# TinyGame_RC1.net
KiCad netlist of a schematic drawn in EAGLE
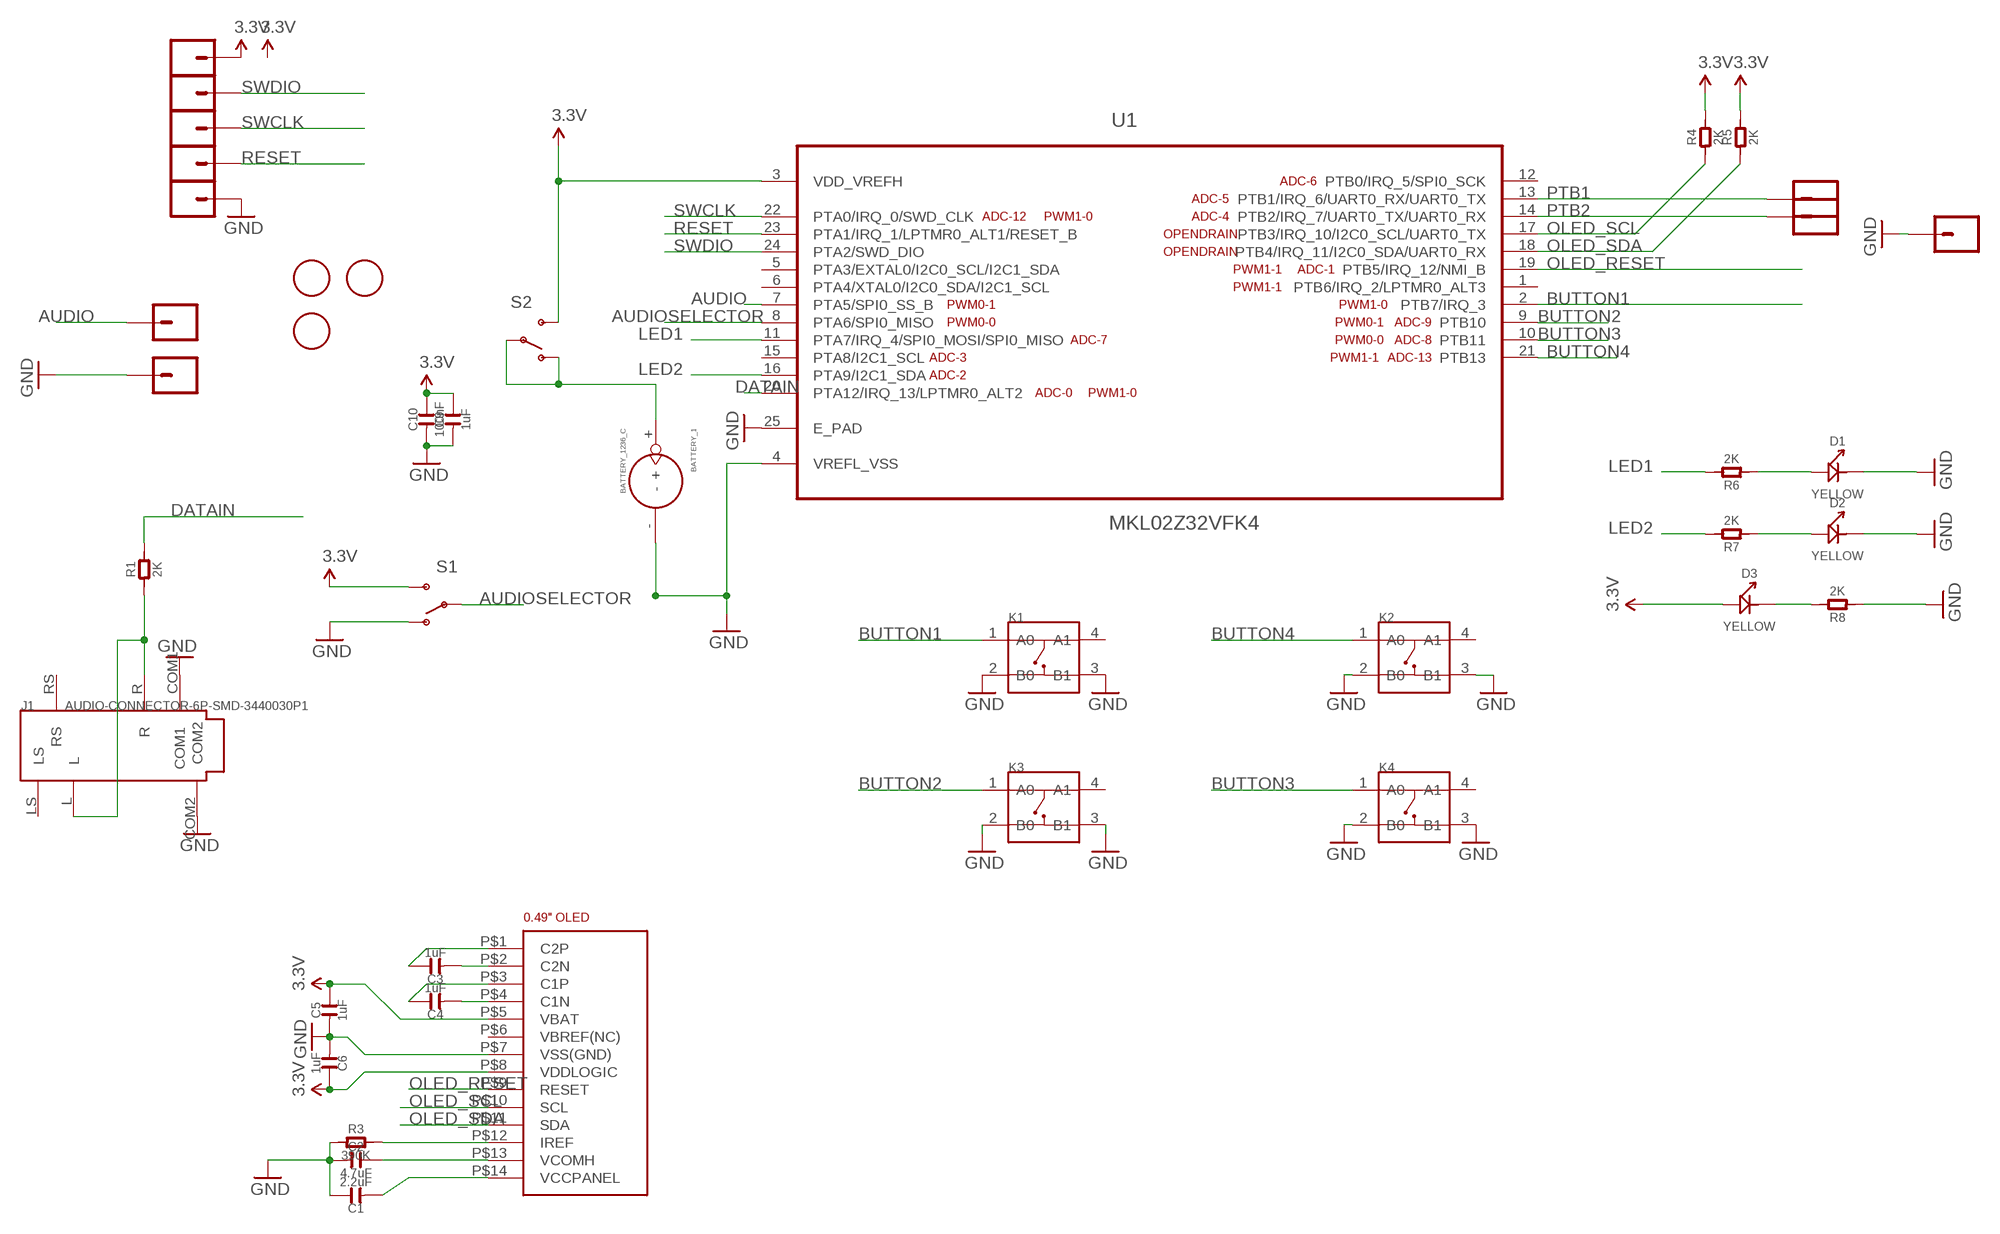
[diagram p0: schematic, sheet 1]

(export (version "E")
  (design (tool "Eeschema 10.0.6"))
  (components
    (comp (ref "AUDIOGND")
      (value "M01SMD-4.5X1.5")
      (footprint "eagle-import:PAD-1.5X4.5")
      (libsource (lib "eagle-import") (part "M01SMD-4.5X1.5"))
    )
    (comp (ref "AUDIOSIG")
      (value "M01SMD-4.5X1.5")
      (footprint "eagle-import:PAD-1.5X4.5")
      (libsource (lib "eagle-import") (part "M01SMD-4.5X1.5"))
    )
    (comp (ref "BATTERY_1")
      (value "BATTERY_1236_C")
      (footprint "eagle-import:BATTERY_1236_C")
      (libsource (lib "eagle-import") (part "BATTERY_1236_C"))
    )
    (comp (ref "C1")
      (value "2.2uF")
      (footprint "eagle-import:C0603")
      (libsource (lib "eagle-import") (part "C-0603"))
    )
    (comp (ref "C2")
      (value "4.7uF")
      (footprint "eagle-import:C0603")
      (libsource (lib "eagle-import") (part "C-0603"))
    )
    (comp (ref "C3")
      (value "1uF")
      (footprint "eagle-import:C0603")
      (libsource (lib "eagle-import") (part "C-0603"))
    )
    (comp (ref "C4")
      (value "1uF")
      (footprint "eagle-import:C0603")
      (libsource (lib "eagle-import") (part "C-0603"))
    )
    (comp (ref "C5")
      (value "1uF")
      (footprint "eagle-import:C0603")
      (libsource (lib "eagle-import") (part "C-0603"))
    )
    (comp (ref "C6")
      (value "1uF")
      (footprint "eagle-import:C0603")
      (libsource (lib "eagle-import") (part "C-0603"))
    )
    (comp (ref "C9")
      (value "1uF")
      (footprint "eagle-import:C0603")
      (libsource (lib "eagle-import") (part "C-0603"))
    )
    (comp (ref "C10")
      (value "100nF")
      (footprint "eagle-import:C0603")
      (libsource (lib "eagle-import") (part "C-0603"))
    )
    (comp (ref "D1")
      (value "YELLOW")
      (footprint "eagle-import:LED0603")
      (libsource (lib "eagle-import") (part "LED"))
    )
    (comp (ref "D2")
      (value "YELLOW")
      (footprint "eagle-import:LED0603")
      (libsource (lib "eagle-import") (part "LED"))
    )
    (comp (ref "D3")
      (value "YELLOW")
      (footprint "eagle-import:LED0603")
      (libsource (lib "eagle-import") (part "LED"))
    )
    (comp (ref "J1")
      (value "AUDIO-CONNECTOR-6P-SMD-3440030P1")
      (footprint "eagle-import:6P-SMD-3.5")
      (libsource (lib "eagle-import") (part "AUDIO-CONNECTOR-6P-SMD-3440030P1"))
    )
    (comp (ref "K1")
      (value "BUTTON-4P-3100010P1")
      (footprint "eagle-import:4P-SMD-6.0X6.0X5.0H")
      (libsource (lib "eagle-import") (part "BUTTON-4P-3100010P1"))
    )
    (comp (ref "K2")
      (value "BUTTON-4P-3100010P1")
      (footprint "eagle-import:4P-SMD-6.0X6.0X5.0H")
      (libsource (lib "eagle-import") (part "BUTTON-4P-3100010P1"))
    )
    (comp (ref "K3")
      (value "BUTTON-4P-3100010P1")
      (footprint "eagle-import:4P-SMD-6.0X6.0X5.0H")
      (libsource (lib "eagle-import") (part "BUTTON-4P-3100010P1"))
    )
    (comp (ref "K4")
      (value "BUTTON-4P-3100010P1")
      (footprint "eagle-import:4P-SMD-6.0X6.0X5.0H")
      (libsource (lib "eagle-import") (part "BUTTON-4P-3100010P1"))
    )
    (comp (ref "PTA6_MISO1")
      (value "M01SMD-4.5X1.5")
      (footprint "eagle-import:PAD-1.5X4.5")
      (libsource (lib "eagle-import") (part "M01SMD-4.5X1.5"))
    )
    (comp (ref "PTA6_MISO2")
      (value "M01SMD-4.5X1.5")
      (footprint "eagle-import:PAD-1.5X4.5")
      (libsource (lib "eagle-import") (part "M01SMD-4.5X1.5"))
    )
    (comp (ref "PTA6_MISO3")
      (value "M01SMD-4.5X1.5")
      (footprint "eagle-import:PAD-1.5X4.5")
      (libsource (lib "eagle-import") (part "M01SMD-4.5X1.5"))
    )
    (comp (ref "PTA6_MISO4")
      (value "M01SMD-4.5X1.5")
      (footprint "eagle-import:PAD-1.5X4.5")
      (libsource (lib "eagle-import") (part "M01SMD-4.5X1.5"))
    )
    (comp (ref "PTA6_MISO5")
      (value "M01SMD-4.5X1.5")
      (footprint "eagle-import:PAD-1.5X4.5")
      (libsource (lib "eagle-import") (part "M01SMD-4.5X1.5"))
    )
    (comp (ref "PTB1_RXTX")
      (value "M01SMD-4.5X1.5")
      (footprint "eagle-import:PAD-1.5X4.5")
      (libsource (lib "eagle-import") (part "M01SMD-4.5X1.5"))
    )
    (comp (ref "PTB2_TXRX")
      (value "M01SMD-4.5X1.5")
      (footprint "eagle-import:PAD-1.5X4.5")
      (libsource (lib "eagle-import") (part "M01SMD-4.5X1.5"))
    )
    (comp (ref "PTB2_TXRX2")
      (value "M01SMD-4.5X1.5")
      (footprint "eagle-import:PAD-1.5X4.5")
      (libsource (lib "eagle-import") (part "M01SMD-4.5X1.5"))
    )
    (comp (ref "R1")
      (value "2K")
      (footprint "eagle-import:R0603")
      (libsource (lib "eagle-import") (part "R-0603"))
    )
    (comp (ref "R3")
      (value "390K")
      (footprint "eagle-import:R0603")
      (libsource (lib "eagle-import") (part "R-0603"))
    )
    (comp (ref "R4")
      (value "2K")
      (footprint "eagle-import:R0603")
      (libsource (lib "eagle-import") (part "R-0603"))
    )
    (comp (ref "R5")
      (value "2K")
      (footprint "eagle-import:R0603")
      (libsource (lib "eagle-import") (part "R-0603"))
    )
    (comp (ref "R6")
      (value "2K")
      (footprint "eagle-import:R0603")
      (libsource (lib "eagle-import") (part "R-0603"))
    )
    (comp (ref "R7")
      (value "2K")
      (footprint "eagle-import:R0603")
      (libsource (lib "eagle-import") (part "R-0603"))
    )
    (comp (ref "R8")
      (value "2K")
      (footprint "eagle-import:R0603")
      (libsource (lib "eagle-import") (part "R-0603"))
    )
    (comp (ref "S1")
      (value "SWITCH-SPDT-SMD-A")
      (footprint "eagle-import:SWITCH-SPST-SMD-A")
      (libsource (lib "eagle-import") (part "SWITCH-SPDT-SMD-A"))
    )
    (comp (ref "S2")
      (value "SWITCH-SPDT-SMD-A")
      (footprint "eagle-import:SWITCH-SPST-SMD-A")
      (libsource (lib "eagle-import") (part "SWITCH-SPDT-SMD-A"))
    )
    (comp (ref "U$1")
      (value "0.49\"OLEDFOLDED")
      (footprint "eagle-import:0.49_-FPC-0.7-14-FOLDED")
      (libsource (lib "eagle-import") (part "0.49{dblquote}OLEDFOLDED"))
    )
    (comp (ref "U$2")
      (value "FIDUCIAL")
      (footprint "eagle-import:FIDUCIAL_1MM")
      (libsource (lib "eagle-import") (part "FIDUCIAL"))
    )
    (comp (ref "U$3")
      (value "FIDUCIAL")
      (footprint "eagle-import:FIDUCIAL_1MM")
      (libsource (lib "eagle-import") (part "FIDUCIAL"))
    )
    (comp (ref "U$4")
      (value "FIDUCIAL")
      (footprint "eagle-import:FIDUCIAL_1MM")
      (libsource (lib "eagle-import") (part "FIDUCIAL"))
    )
    (comp (ref "U1")
      (value "MKL02Z32VFK4")
      (footprint "eagle-import:QFN50P400X400X100-25N")
      (libsource (lib "eagle-import") (part "MKL02Z32VFK4"))
    )
  )
  (nets
    (net (code "1") (name "/AUDIO") (class "Default")
      (node (ref "AUDIOSIG") (pin "P$1") (pinfunction "1_P$1") (pintype "passive"))
      (node (ref "U1") (pin "7") (pinfunction "PTA5/SPI0_SS_B_7") (pintype "bidirectional"))
    )
    (net (code "2") (name "/AUDIOSELECTOR") (class "Default")
      (node (ref "S1") (pin "2") (pinfunction "P_2") (pintype "passive"))
      (node (ref "U1") (pin "8") (pinfunction "PTA6/SPI0_MISO_8") (pintype "bidirectional"))
    )
    (net (code "3") (name "/BUTTON1") (class "Default")
      (node (ref "K1") (pin "1") (pinfunction "A0_1") (pintype "bidirectional"))
      (node (ref "U1") (pin "2") (pinfunction "PTB7/IRQ_3_2") (pintype "bidirectional"))
    )
    (net (code "4") (name "/BUTTON2") (class "Default")
      (node (ref "K3") (pin "1") (pinfunction "A0_1") (pintype "bidirectional"))
      (node (ref "U1") (pin "9") (pinfunction "PTB10_9") (pintype "bidirectional"))
    )
    (net (code "5") (name "/BUTTON3") (class "Default")
      (node (ref "K4") (pin "1") (pinfunction "A0_1") (pintype "bidirectional"))
      (node (ref "U1") (pin "10") (pinfunction "PTB11_10") (pintype "bidirectional"))
    )
    (net (code "6") (name "/BUTTON4") (class "Default")
      (node (ref "K2") (pin "1") (pinfunction "A0_1") (pintype "bidirectional"))
      (node (ref "U1") (pin "21") (pinfunction "PTB13_21") (pintype "bidirectional"))
    )
    (net (code "7") (name "/DATAIN") (class "Default")
      (node (ref "R1") (pin "2") (pinfunction "2_2") (pintype "bidirectional"))
      (node (ref "U1") (pin "20") (pinfunction "PTA12/IRQ_13/LPTMR0_ALT2_20") (pintype "bidirectional"))
    )
    (net (code "8") (name "/LED1") (class "Default")
      (node (ref "R6") (pin "2") (pinfunction "2_2") (pintype "bidirectional"))
      (node (ref "U1") (pin "11") (pinfunction "PTA7/IRQ_4/SPI0_MOSI/SPI0_MISO_11") (pintype "bidirectional"))
    )
    (net (code "9") (name "/LED2") (class "Default")
      (node (ref "R7") (pin "2") (pinfunction "2_2") (pintype "bidirectional"))
      (node (ref "U1") (pin "16") (pinfunction "PTA9/I2C1_SDA_16") (pintype "bidirectional"))
    )
    (net (code "10") (name "/OLED_RESET") (class "Default")
      (node (ref "U$1") (pin "P$9") (pinfunction "RESET_P$9") (pintype "bidirectional"))
      (node (ref "U1") (pin "19") (pinfunction "PTB5/IRQ_12/NMI_B_19") (pintype "bidirectional"))
    )
    (net (code "11") (name "/OLED_SCL") (class "Default")
      (node (ref "R4") (pin "1") (pinfunction "1_1") (pintype "bidirectional"))
      (node (ref "U$1") (pin "P$10") (pinfunction "SCL_P$10") (pintype "bidirectional"))
      (node (ref "U1") (pin "17") (pinfunction "PTB3/IRQ_10/I2C0_SCL/UART0_TX_17") (pintype "bidirectional"))
    )
    (net (code "12") (name "/OLED_SDA") (class "Default")
      (node (ref "R5") (pin "1") (pinfunction "1_1") (pintype "bidirectional"))
      (node (ref "U$1") (pin "P$11") (pinfunction "SDA_P$11") (pintype "bidirectional"))
      (node (ref "U1") (pin "18") (pinfunction "PTB4/IRQ_11/I2C0_SDA/UART0_RX_18") (pintype "bidirectional"))
    )
    (net (code "13") (name "/PTB1") (class "Default")
      (node (ref "PTB1_RXTX") (pin "P$1") (pinfunction "1_P$1") (pintype "passive"))
      (node (ref "U1") (pin "13") (pinfunction "PTB1/IRQ_6/UART0_RX/UART0_TX_13") (pintype "bidirectional"))
    )
    (net (code "14") (name "/PTB2") (class "Default")
      (node (ref "PTB2_TXRX") (pin "P$1") (pinfunction "1_P$1") (pintype "passive"))
      (node (ref "U1") (pin "14") (pinfunction "PTB2/IRQ_7/UART0_TX/UART0_RX_14") (pintype "bidirectional"))
    )
    (net (code "15") (name "/RESET") (class "Default")
      (node (ref "PTA6_MISO4") (pin "P$1") (pinfunction "1_P$1") (pintype "passive"))
      (node (ref "U1") (pin "23") (pinfunction "PTA1/IRQ_1/LPTMR0_ALT1/RESET_B_23") (pintype "bidirectional"))
    )
    (net (code "16") (name "/SWCLK") (class "Default")
      (node (ref "PTA6_MISO3") (pin "P$1") (pinfunction "1_P$1") (pintype "passive"))
      (node (ref "U1") (pin "22") (pinfunction "PTA0/IRQ_0/SWD_CLK_22") (pintype "bidirectional"))
    )
    (net (code "17") (name "/SWDIO") (class "Default")
      (node (ref "PTA6_MISO2") (pin "P$1") (pinfunction "1_P$1") (pintype "passive"))
      (node (ref "U1") (pin "24") (pinfunction "PTA2/SWD_DIO_24") (pintype "bidirectional"))
    )
    (net (code "18") (name "3.3V") (class "Default")
      (node (ref "C10") (pin "2") (pinfunction "2_2") (pintype "bidirectional"))
      (node (ref "C5") (pin "2") (pinfunction "2_2") (pintype "bidirectional"))
      (node (ref "C6") (pin "2") (pinfunction "2_2") (pintype "bidirectional"))
      (node (ref "C9") (pin "2") (pinfunction "2_2") (pintype "bidirectional"))
      (node (ref "D3") (pin "+") (pinfunction "+_+") (pintype "passive"))
      (node (ref "PTA6_MISO1") (pin "P$1") (pinfunction "1_P$1") (pintype "passive"))
      (node (ref "R4") (pin "2") (pinfunction "2_2") (pintype "bidirectional"))
      (node (ref "R5") (pin "2") (pinfunction "2_2") (pintype "bidirectional"))
      (node (ref "S1") (pin "3") (pinfunction "S_3") (pintype "passive"))
      (node (ref "S2") (pin "3") (pinfunction "S_3") (pintype "passive"))
      (node (ref "U$1") (pin "P$5") (pinfunction "VBAT_P$5") (pintype "bidirectional"))
      (node (ref "U$1") (pin "P$8") (pinfunction "VDDLOGIC_P$8") (pintype "bidirectional"))
      (node (ref "U1") (pin "3") (pinfunction "VDD_VREFH_3") (pintype "power_in"))
    )
    (net (code "19") (name "GND") (class "Default")
      (node (ref "AUDIOGND") (pin "P$1") (pinfunction "1_P$1") (pintype "passive"))
      (node (ref "BATTERY_1") (pin "-") (pinfunction "-_-") (pintype "bidirectional"))
      (node (ref "C1") (pin "2") (pinfunction "2_2") (pintype "bidirectional"))
      (node (ref "C10") (pin "1") (pinfunction "1_1") (pintype "bidirectional"))
      (node (ref "C2") (pin "1") (pinfunction "1_1") (pintype "bidirectional"))
      (node (ref "C5") (pin "1") (pinfunction "1_1") (pintype "bidirectional"))
      (node (ref "C6") (pin "1") (pinfunction "1_1") (pintype "bidirectional"))
      (node (ref "C9") (pin "1") (pinfunction "1_1") (pintype "bidirectional"))
      (node (ref "D1") (pin "-") (pinfunction "-_-") (pintype "passive"))
      (node (ref "D2") (pin "-") (pinfunction "-_-") (pintype "passive"))
      (node (ref "J1") (pin "COM1") (pinfunction "COM1_COM1") (pintype "bidirectional"))
      (node (ref "J1") (pin "COM2") (pinfunction "COM2_COM2") (pintype "bidirectional"))
      (node (ref "K1") (pin "2") (pinfunction "B0_2") (pintype "bidirectional"))
      (node (ref "K1") (pin "3") (pinfunction "B1_3") (pintype "bidirectional"))
      (node (ref "K2") (pin "2") (pinfunction "B0_2") (pintype "bidirectional"))
      (node (ref "K2") (pin "3") (pinfunction "B1_3") (pintype "bidirectional"))
      (node (ref "K3") (pin "2") (pinfunction "B0_2") (pintype "bidirectional"))
      (node (ref "K3") (pin "3") (pinfunction "B1_3") (pintype "bidirectional"))
      (node (ref "K4") (pin "2") (pinfunction "B0_2") (pintype "bidirectional"))
      (node (ref "K4") (pin "3") (pinfunction "B1_3") (pintype "bidirectional"))
      (node (ref "PTA6_MISO5") (pin "P$1") (pinfunction "1_P$1") (pintype "passive"))
      (node (ref "PTB2_TXRX2") (pin "P$1") (pinfunction "1_P$1") (pintype "passive"))
      (node (ref "R3") (pin "1") (pinfunction "1_1") (pintype "bidirectional"))
      (node (ref "R8") (pin "1") (pinfunction "1_1") (pintype "bidirectional"))
      (node (ref "S1") (pin "1") (pinfunction "O_1") (pintype "passive"))
      (node (ref "U$1") (pin "P$7") (pinfunction "VSS(GND)_P$7") (pintype "bidirectional"))
      (node (ref "U1") (pin "25") (pinfunction "E_PAD_25") (pintype "passive"))
      (node (ref "U1") (pin "4") (pinfunction "VREFL_VSS_4") (pintype "passive"))
    )
    (net (code "20") (name "Net-(D1-Pad+)") (class "Default")
      (node (ref "D1") (pin "+") (pinfunction "+_+") (pintype "passive"))
      (node (ref "R6") (pin "1") (pinfunction "1_1") (pintype "bidirectional"))
    )
    (net (code "21") (name "Net-(D2-Pad+)") (class "Default")
      (node (ref "D2") (pin "+") (pinfunction "+_+") (pintype "passive"))
      (node (ref "R7") (pin "1") (pinfunction "1_1") (pintype "bidirectional"))
    )
    (net (code "22") (name "Net-(D3-Pad-)") (class "Default")
      (node (ref "D3") (pin "-") (pinfunction "-_-") (pintype "passive"))
      (node (ref "R8") (pin "2") (pinfunction "2_2") (pintype "bidirectional"))
    )
    (net (code "23") (name "Net-(J1-PadL)") (class "Default")
      (node (ref "J1") (pin "L") (pinfunction "L_L") (pintype "bidirectional"))
      (node (ref "J1") (pin "R") (pinfunction "R_R") (pintype "bidirectional"))
      (node (ref "R1") (pin "1") (pinfunction "1_1") (pintype "bidirectional"))
    )
    (net (code "24") (name "Net-(S2-O)") (class "Default")
      (node (ref "BATTERY_1") (pin "+") (pinfunction "+_+") (pintype "bidirectional"))
      (node (ref "S2") (pin "1") (pinfunction "O_1") (pintype "passive"))
      (node (ref "S2") (pin "2") (pinfunction "P_2") (pintype "passive"))
    )
    (net (code "25") (name "Net-(U$1-C1N)") (class "Default")
      (node (ref "C4") (pin "1") (pinfunction "1_1") (pintype "bidirectional"))
      (node (ref "U$1") (pin "P$4") (pinfunction "C1N_P$4") (pintype "bidirectional"))
    )
    (net (code "26") (name "Net-(U$1-C1P)") (class "Default")
      (node (ref "C4") (pin "2") (pinfunction "2_2") (pintype "bidirectional"))
      (node (ref "U$1") (pin "P$3") (pinfunction "C1P_P$3") (pintype "bidirectional"))
    )
    (net (code "27") (name "Net-(U$1-C2N)") (class "Default")
      (node (ref "C3") (pin "1") (pinfunction "1_1") (pintype "bidirectional"))
      (node (ref "U$1") (pin "P$2") (pinfunction "C2N_P$2") (pintype "bidirectional"))
    )
    (net (code "28") (name "Net-(U$1-C2P)") (class "Default")
      (node (ref "C3") (pin "2") (pinfunction "2_2") (pintype "bidirectional"))
      (node (ref "U$1") (pin "P$1") (pinfunction "C2P_P$1") (pintype "bidirectional"))
    )
    (net (code "29") (name "Net-(U$1-IREF)") (class "Default")
      (node (ref "R3") (pin "2") (pinfunction "2_2") (pintype "bidirectional"))
      (node (ref "U$1") (pin "P$12") (pinfunction "IREF_P$12") (pintype "bidirectional"))
    )
    (net (code "30") (name "Net-(U$1-VCCPANEL)") (class "Default")
      (node (ref "C1") (pin "1") (pinfunction "1_1") (pintype "bidirectional"))
      (node (ref "U$1") (pin "P$14") (pinfunction "VCCPANEL_P$14") (pintype "bidirectional"))
    )
    (net (code "31") (name "Net-(U$1-VCOMH)") (class "Default")
      (node (ref "C2") (pin "2") (pinfunction "2_2") (pintype "bidirectional"))
      (node (ref "U$1") (pin "P$13") (pinfunction "VCOMH_P$13") (pintype "bidirectional"))
    )
    (net (code "32") (name "unconnected-(J1-PadLS)") (class "Default")
      (node (ref "J1") (pin "LS") (pinfunction "LS_LS") (pintype "bidirectional"))
    )
    (net (code "33") (name "unconnected-(J1-PadRS)") (class "Default")
      (node (ref "J1") (pin "RS") (pinfunction "RS_RS") (pintype "bidirectional"))
    )
    (net (code "34") (name "unconnected-(K1-A1-Pad4)") (class "Default")
      (node (ref "K1") (pin "4") (pinfunction "A1_4") (pintype "bidirectional"))
    )
    (net (code "35") (name "unconnected-(K2-A1-Pad4)") (class "Default")
      (node (ref "K2") (pin "4") (pinfunction "A1_4") (pintype "bidirectional"))
    )
    (net (code "36") (name "unconnected-(K3-A1-Pad4)") (class "Default")
      (node (ref "K3") (pin "4") (pinfunction "A1_4") (pintype "bidirectional"))
    )
    (net (code "37") (name "unconnected-(K4-A1-Pad4)") (class "Default")
      (node (ref "K4") (pin "4") (pinfunction "A1_4") (pintype "bidirectional"))
    )
    (net (code "38") (name "unconnected-(U$1-VBREF(NC)-PadP$6)") (class "Default")
      (node (ref "U$1") (pin "P$6") (pinfunction "VBREF(NC)_P$6") (pintype "bidirectional"))
    )
    (net (code "39") (name "unconnected-(U1-PTA3{slash}EXTAL0{slash}I2C0_SCL{slash}I2C1_SDA-Pad5)") (class "Default")
      (node (ref "U1") (pin "5") (pinfunction "PTA3/EXTAL0/I2C0_SCL/I2C1_SDA_5") (pintype "bidirectional"))
    )
    (net (code "40") (name "unconnected-(U1-PTA4{slash}XTAL0{slash}I2C0_SDA{slash}I2C1_SCL-Pad6)") (class "Default")
      (node (ref "U1") (pin "6") (pinfunction "PTA4/XTAL0/I2C0_SDA/I2C1_SCL_6") (pintype "bidirectional"))
    )
    (net (code "41") (name "unconnected-(U1-PTA8{slash}I2C1_SCL-Pad15)") (class "Default")
      (node (ref "U1") (pin "15") (pinfunction "PTA8/I2C1_SCL_15") (pintype "bidirectional"))
    )
    (net (code "42") (name "unconnected-(U1-PTB0{slash}IRQ_5{slash}SPI0_SCK-Pad12)") (class "Default")
      (node (ref "U1") (pin "12") (pinfunction "PTB0/IRQ_5/SPI0_SCK_12") (pintype "bidirectional"))
    )
    (net (code "43") (name "unconnected-(U1-PTB6{slash}IRQ_2{slash}LPTMR0_ALT3-Pad1)") (class "Default")
      (node (ref "U1") (pin "1") (pinfunction "PTB6/IRQ_2/LPTMR0_ALT3_1") (pintype "bidirectional"))
    )
  )
)
